# clock.net
KiCad netlist of a schematic drawn in Altium Designer
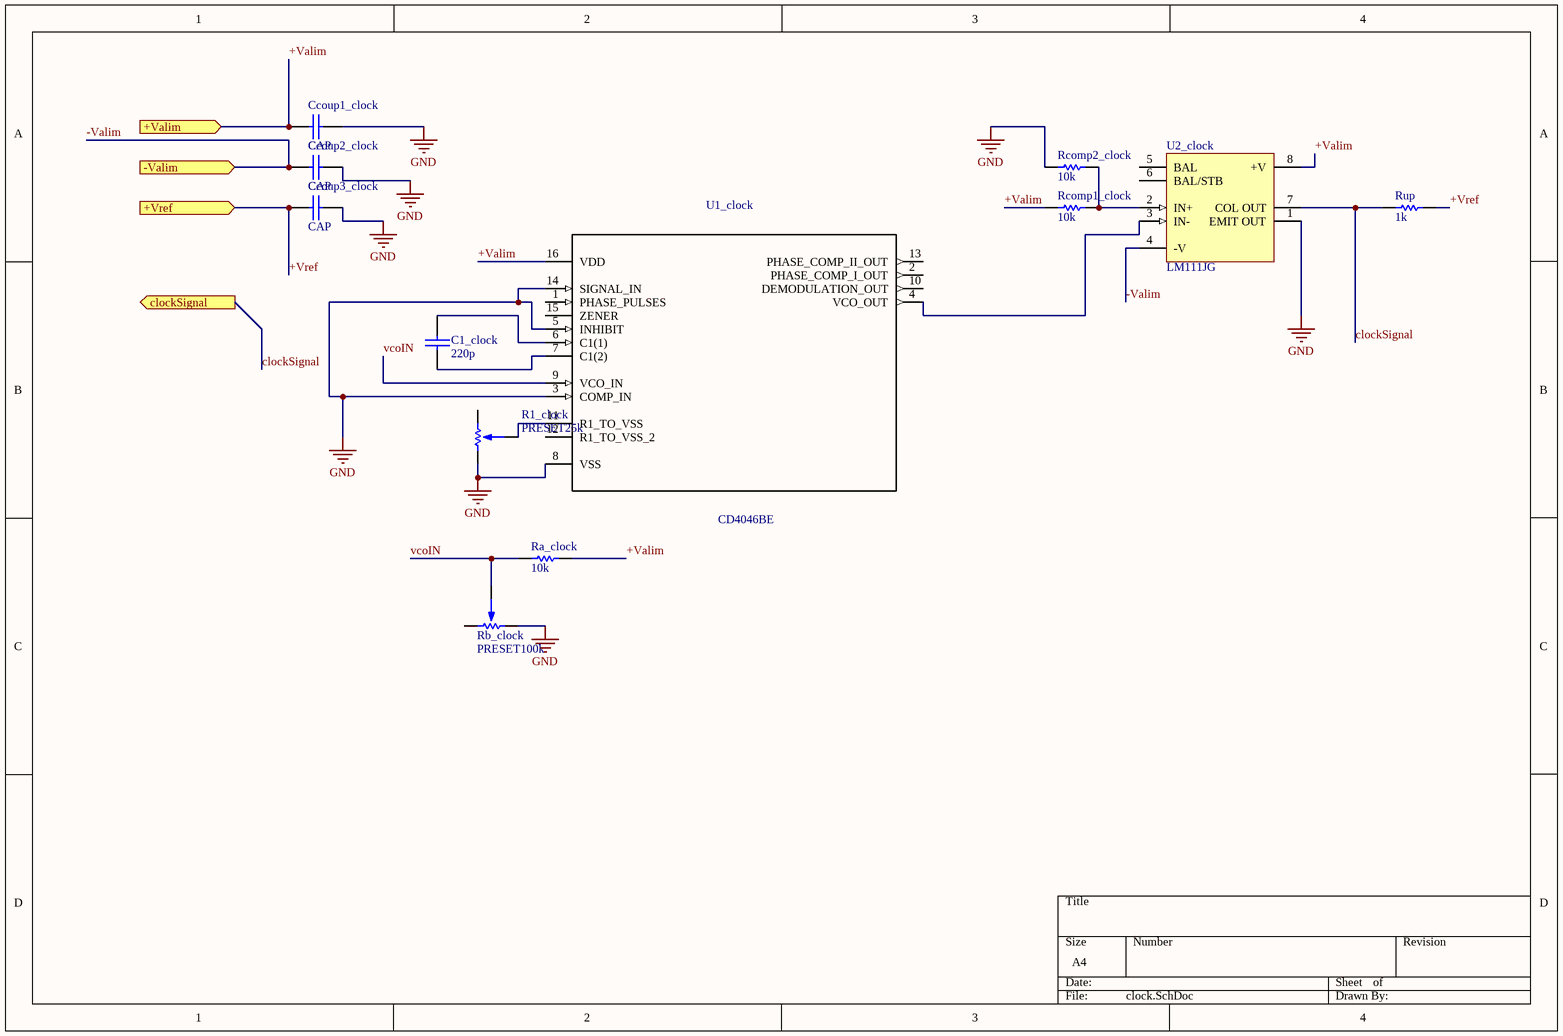
[diagram p0: clock.SchDoc]

(export (version "E")
  (design (tool "Eeschema 10.0.6"))
  (components
    (comp (ref "C1_clock") (value "220p") (footprint "CAP200") (libsource (lib "LIBEBAL") (part "CAP")))
    (comp (ref "Ccoup1_clock") (value "CAP") (footprint "CAP200") (libsource (lib "LIBEBAL") (part "CAP")))
    (comp (ref "Ccoup2_clock") (value "CAP") (footprint "CAP200") (libsource (lib "LIBEBAL") (part "CAP")))
    (comp (ref "Ccoup3_clock") (value "CAP") (footprint "CAP200") (libsource (lib "LIBEBAL") (part "CAP")))
    (comp (ref "R1_clock")
      (value "PRESET25k")
      (footprint "PRESET V")
      (libsource (lib "LIBEBAL") (part "PRESET"))
    )
    (comp (ref "Ra_clock") (value "10k") (footprint "RES300") (libsource (lib "LIBEBAL") (part "RES")))
    (comp (ref "Rb_clock")
      (value "PRESET100k")
      (footprint "PRESET V")
      (libsource (lib "LIBEBAL") (part "PRESET"))
    )
    (comp (ref "Rcomp1_clock") (value "10k") (footprint "RES300") (libsource (lib "LIBEBAL") (part "RES")))
    (comp (ref "Rcomp2_clock") (value "10k") (footprint "RES300") (libsource (lib "LIBEBAL") (part "RES")))
    (comp (ref "Rup") (value "1k") (footprint "RES300") (libsource (lib "LIBEBAL") (part "RES")))
    (comp (ref "U1_clock")
      (value "CD4046BE")
      (footprint "DIP254P762X508-16")
      (description "Logic - Phase-Locked-Loops and Oscillators Micropower PLL")
      (fields (field (name "MF") "Texas Instruments"))
      (libsource (lib "CD4046BE") (part "CD4046BE"))
    )
    (comp (ref "U2_clock")
      (value "LM111JG")
      (footprint "JG008")
      (description "Differential Comparator with Strobe")
      (fields (field (name "PUBLISHER") "Altium Limited"))
      (libsource (lib "TI Analog Comparator") (part "LM111JG"))
    )
  )
  (nets
    (net (code "1") (name "/+Valim") (class "Default")
      (node (ref "Ccoup1_clock") (pin "1") (pinfunction "1_1") (pintype "passive"))
      (node (ref "Ra_clock") (pin "2") (pinfunction "2_2") (pintype "passive"))
      (node (ref "Rcomp1_clock") (pin "1") (pinfunction "1_1") (pintype "passive"))
      (node (ref "U1_clock") (pin "16") (pinfunction "VDD_16") (pintype "power_in"))
      (node (ref "U2_clock") (pin "8") (pinfunction "+V_8") (pintype "power_in"))
    )
    (net (code "2") (name "/+Vref") (class "Default")
      (node (ref "Ccoup3_clock") (pin "1") (pinfunction "1_1") (pintype "passive"))
      (node (ref "Rup") (pin "2") (pinfunction "2_2") (pintype "passive"))
    )
    (net (code "3") (name "/-Valim") (class "Default")
      (node (ref "Ccoup2_clock") (pin "1") (pinfunction "1_1") (pintype "passive"))
      (node (ref "U2_clock") (pin "4") (pinfunction "-V_4") (pintype "power_in"))
    )
    (net (code "4") (name "/clockSignal") (class "Default")
      (node (ref "Rup") (pin "1") (pinfunction "1_1") (pintype "passive"))
      (node (ref "U2_clock") (pin "7") (pinfunction "COL_OUT_7") (pintype "open_collector"))
    )
    (net (code "5") (name "/vcoIN") (class "Default")
      (node (ref "Ra_clock") (pin "1") (pinfunction "1_1") (pintype "passive"))
      (node (ref "Rb_clock") (pin "2") (pinfunction "2_2") (pintype "passive"))
      (node (ref "U1_clock") (pin "9") (pinfunction "VCO_IN_9") (pintype "input"))
    )
    (net (code "6") (name "GND") (class "Default")
      (node (ref "Ccoup1_clock") (pin "2") (pinfunction "2_2") (pintype "passive"))
      (node (ref "Ccoup2_clock") (pin "2") (pinfunction "2_2") (pintype "passive"))
      (node (ref "Ccoup3_clock") (pin "2") (pinfunction "2_2") (pintype "passive"))
      (node (ref "R1_clock") (pin "3") (pinfunction "3_3") (pintype "passive"))
      (node (ref "Rb_clock") (pin "3") (pinfunction "3_3") (pintype "passive"))
      (node (ref "Rcomp2_clock") (pin "1") (pinfunction "1_1") (pintype "passive"))
      (node (ref "U1_clock") (pin "14") (pinfunction "SIGNAL_IN_14") (pintype "input"))
      (node (ref "U1_clock") (pin "3") (pinfunction "COMP_IN_3") (pintype "input"))
      (node (ref "U1_clock") (pin "5") (pinfunction "INHIBIT_5") (pintype "input"))
      (node (ref "U1_clock") (pin "8") (pinfunction "VSS_8") (pintype "power_in"))
      (node (ref "U2_clock") (pin "1") (pinfunction "EMIT_OUT_1") (pintype "open_emitter"))
    )
    (net (code "7") (name "Net-(U1_clock-C1(1))") (class "Default")
      (node (ref "C1_clock") (pin "1") (pinfunction "1_1") (pintype "passive"))
      (node (ref "U1_clock") (pin "6") (pinfunction "C1(1)_6") (pintype "input"))
    )
    (net (code "8") (name "Net-(U1_clock-C1(2))") (class "Default")
      (node (ref "C1_clock") (pin "2") (pinfunction "2_2") (pintype "passive"))
      (node (ref "U1_clock") (pin "7") (pinfunction "C1(2)_7") (pintype "passive"))
    )
    (net (code "9") (name "Net-(U1_clock-R1_TO_VSS)") (class "Default")
      (node (ref "R1_clock") (pin "2") (pinfunction "2_2") (pintype "passive"))
      (node (ref "U1_clock") (pin "11") (pinfunction "R1_TO_VSS_11") (pintype "passive"))
    )
    (net (code "10") (name "Net-(U1_clock-VCO_OUT)") (class "Default")
      (node (ref "U1_clock") (pin "4") (pinfunction "VCO_OUT_4") (pintype "output"))
      (node (ref "U2_clock") (pin "3") (pinfunction "IN-_3") (pintype "input"))
    )
    (net (code "11") (name "Net-(U2_clock-IN+)") (class "Default")
      (node (ref "Rcomp1_clock") (pin "2") (pinfunction "2_2") (pintype "passive"))
      (node (ref "Rcomp2_clock") (pin "2") (pinfunction "2_2") (pintype "passive"))
      (node (ref "U2_clock") (pin "2") (pinfunction "IN+_2") (pintype "input"))
    )
    (net (code "12") (name "unconnected-(R1_clock-Pad1)") (class "Default")
      (node (ref "R1_clock") (pin "1") (pinfunction "1_1") (pintype "passive"))
    )
    (net (code "13") (name "unconnected-(Rb_clock-Pad1)") (class "Default")
      (node (ref "Rb_clock") (pin "1") (pinfunction "1_1") (pintype "passive"))
    )
    (net (code "14") (name "unconnected-(U1_clock-DEMODULATION_OUT-Pad10)") (class "Default")
      (node (ref "U1_clock") (pin "10") (pinfunction "DEMODULATION_OUT_10") (pintype "output"))
    )
    (net (code "15") (name "unconnected-(U1_clock-PHASE_COMP_II_OUT-Pad13)") (class "Default")
      (node (ref "U1_clock") (pin "13") (pinfunction "PHASE_COMP_II_OUT_13") (pintype "output"))
    )
    (net (code "16") (name "unconnected-(U1_clock-PHASE_COMP_I_OUT-Pad2)") (class "Default")
      (node (ref "U1_clock") (pin "2") (pinfunction "PHASE_COMP_I_OUT_2") (pintype "output"))
    )
    (net (code "17") (name "unconnected-(U1_clock-PHASE_PULSES-Pad1)") (class "Default")
      (node (ref "U1_clock") (pin "1") (pinfunction "PHASE_PULSES_1") (pintype "input"))
    )
    (net (code "18") (name "unconnected-(U1_clock-R1_TO_VSS_2-Pad12)") (class "Default")
      (node (ref "U1_clock") (pin "12") (pinfunction "R1_TO_VSS_2_12") (pintype "passive"))
    )
    (net (code "19") (name "unconnected-(U1_clock-ZENER-Pad15)") (class "Default")
      (node (ref "U1_clock") (pin "15") (pinfunction "ZENER_15") (pintype "passive"))
    )
    (net (code "20") (name "unconnected-(U2_clock-BAL-Pad5)") (class "Default")
      (node (ref "U2_clock") (pin "5") (pinfunction "BAL_5") (pintype "passive"))
    )
    (net (code "21") (name "unconnected-(U2_clock-BAL{slash}STB-Pad6)") (class "Default")
      (node (ref "U2_clock") (pin "6") (pinfunction "BAL/STB_6") (pintype "passive"))
    )
  )
)
